# LM1117_3V3_800mA.net
KiCad netlist of a schematic drawn in Altium Designer
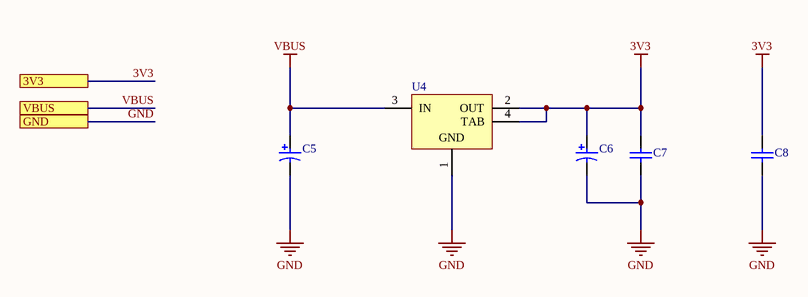
[diagram p0: LM1117_3V3_800mA.SchDoc]

(export (version "E")
  (design (tool "Eeschema 10.0.6"))
  (components
    (comp (ref "C5")
      (value "T491A106K016AT")
      (footprint "KEMT-A-3216-18-2_N")
      (description "Capacitor, Tantalum, 10 uF, +/- 10%, 16 V, -55 to 125 degC, 2-Pin SMD (1206), RoHS, Tape and Reel")
      (fields (field (name "VOLTAGE") "16VDC") (field (name "MANUFACTURER") "Kemet"))
      (libsource (lib "Altium Content Vault") (part "CAP-P-2"))
    )
    (comp (ref "C6")
      (value "T491A106K016AT")
      (footprint "KEMT-A-3216-18-2_N")
      (description "Capacitor, Tantalum, 10 uF, +/- 10%, 16 V, -55 to 125 degC, 2-Pin SMD (1206), RoHS, Tape and Reel")
      (fields (field (name "VOLTAGE") "16VDC") (field (name "MANUFACTURER") "Kemet"))
      (libsource (lib "Altium Content Vault") (part "CAP-P-2"))
    )
    (comp (ref "C7")
      (value "C0805C105K4RAC7800")
      (footprint "CAPC2013X145X50NL20T25")
      (description "1µF ±10% 16V Ceramic Capacitor X7R 0805 (2012 Metric)")
      (fields (field (name "MANUFACTURER") "Kemet"))
      (libsource (lib "Altium Content Vault") (part "CAP"))
    )
    (comp (ref "C8")
      (value "C0805C106K4PACTU")
      (footprint "CAPC2013X140X50NL20T25")
      (description "10µF ±10% 16V Ceramic Capacitor X5R 0805 (2012 Metric)")
      (fields (field (name "PART NUMBER") "CL21A106KOQNNNG"))
      (libsource (lib "Altium Content Vault") (part "CAP"))
    )
    (comp (ref "U4")
      (value "LM1117MPX-3.3/NOPB")
      (footprint "DCY0004A_N")
      (description "800mA Low-Dropout Linear Regulator, 4-pin SOT-223, Pb-Free")
      (fields (field (name "MANUFACTURER") "Texas Instruments"))
      (libsource (lib "Altium Content Vault") (part "PM-REG-LM1086-SOT4"))
    )
  )
  (nets
    (net (code "1") (name "3V3") (class "Default")
      (node (ref "C6") (pin "1") (pinfunction "1_1") (pintype "passive"))
      (node (ref "C7") (pin "2") (pinfunction "2_2") (pintype "passive"))
      (node (ref "C8") (pin "2") (pinfunction "2_2") (pintype "passive"))
      (node (ref "U4") (pin "2") (pinfunction "OUT_2") (pintype "power_in"))
      (node (ref "U4") (pin "4") (pinfunction "TAB_4") (pintype "power_in"))
    )
    (net (code "2") (name "GND") (class "Default")
      (node (ref "C5") (pin "2") (pinfunction "2_2") (pintype "passive"))
      (node (ref "C6") (pin "2") (pinfunction "2_2") (pintype "passive"))
      (node (ref "C7") (pin "1") (pinfunction "1_1") (pintype "passive"))
      (node (ref "C8") (pin "1") (pinfunction "1_1") (pintype "passive"))
      (node (ref "U4") (pin "1") (pinfunction "GND_1") (pintype "power_in"))
    )
    (net (code "3") (name "VBUS") (class "Default")
      (node (ref "C5") (pin "1") (pinfunction "1_1") (pintype "passive"))
      (node (ref "U4") (pin "3") (pinfunction "IN_3") (pintype "power_in"))
    )
  )
)
